# pamiec_zewnetrzna.net
KiCad netlist of a schematic drawn in Altium Designer
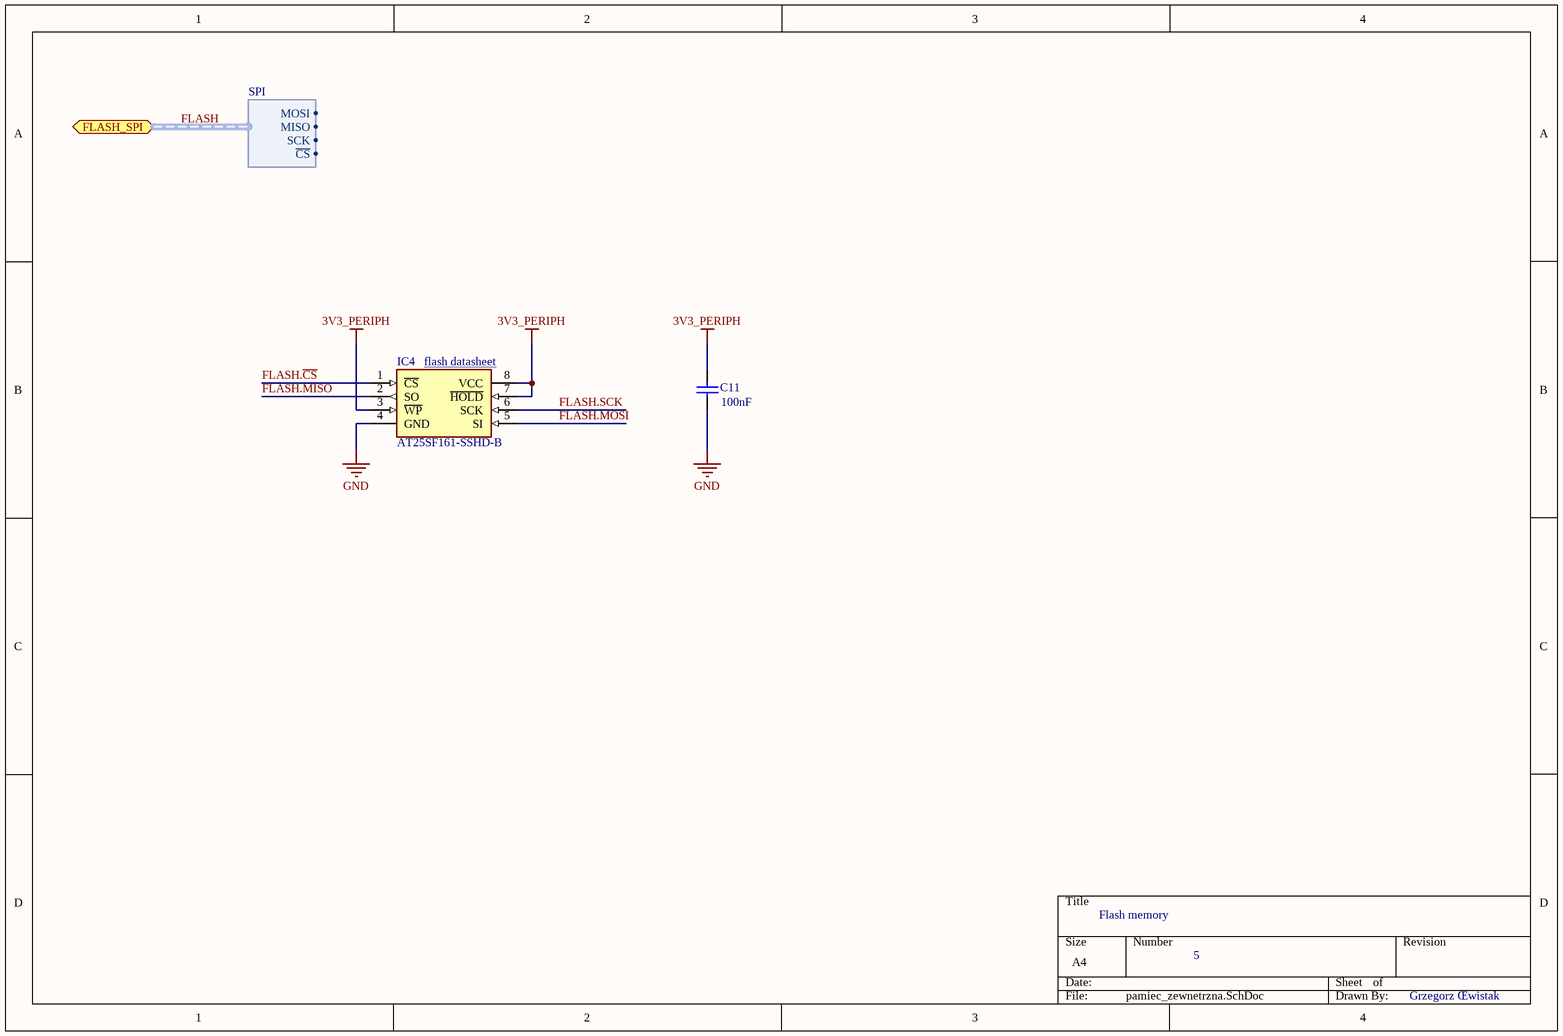
[diagram p0: pamiec_zewnetrzna.SchDoc]

(export (version "E")
  (design (tool "Eeschema 10.0.6"))
  (components
    (comp (ref "C11")
      (value "100nF")
      (footprint "C0805")
      (description "Capacitor")
      (fields (field (name "Comment") "Cap") (field (name "PUBLISHER") "Altium Limited"))
      (libsource (lib "Miscellaneous Devices") (part "Cap"))
    )
    (comp (ref "IC4")
      (value "AT25SF161-SSHD-B")
      (footprint "SOIC127P600X175-8N")
      (description "flash memory SPI")
      (fields
        (field (name "MANUFACTURER_PART_NUMBER") "AT25SF081-SSHD-B")
        (field (name "MOUSER PART NUMBER") "988-AT25SF081-SSHD-B")
      )
      (libsource (lib "lib") (part "AT25SF081-SSHD-B"))
    )
  )
  (nets
    (net (code "2") (name "/FLASH.MISO") (class "Default")
      (node (ref "IC4") (pin "2") (pinfunction "SO_2") (pintype "output"))
    )
    (net (code "3") (name "/FLASH.MOSI") (class "Default")
      (node (ref "IC4") (pin "5") (pinfunction "SI_5") (pintype "input"))
    )
    (net (code "4") (name "/FLASH.SCK") (class "Default")
      (node (ref "IC4") (pin "6") (pinfunction "SCK_6") (pintype "input"))
    )
    (net (code "5") (name "/FLASH.~{CS}") (class "Default")
      (node (ref "IC4") (pin "1") (pinfunction "~{CS}_1") (pintype "input"))
    )
    (net (code "7") (name "3V3_PERIPH") (class "Default")
      (node (ref "C11") (pin "2") (pinfunction "2_2") (pintype "passive"))
      (node (ref "IC4") (pin "3") (pinfunction "~{WP}_3") (pintype "input"))
      (node (ref "IC4") (pin "7") (pinfunction "~{HOLD}_7") (pintype "input"))
      (node (ref "IC4") (pin "8") (pinfunction "VCC_8") (pintype "power_in"))
    )
    (net (code "8") (name "GND") (class "Default")
      (node (ref "C11") (pin "1") (pinfunction "1_1") (pintype "passive"))
      (node (ref "IC4") (pin "4") (pinfunction "GND_4") (pintype "power_in"))
    )
  )
)
